# ESP32-WROOM32D_Module.net
KiCad netlist of a schematic drawn in Altium Designer
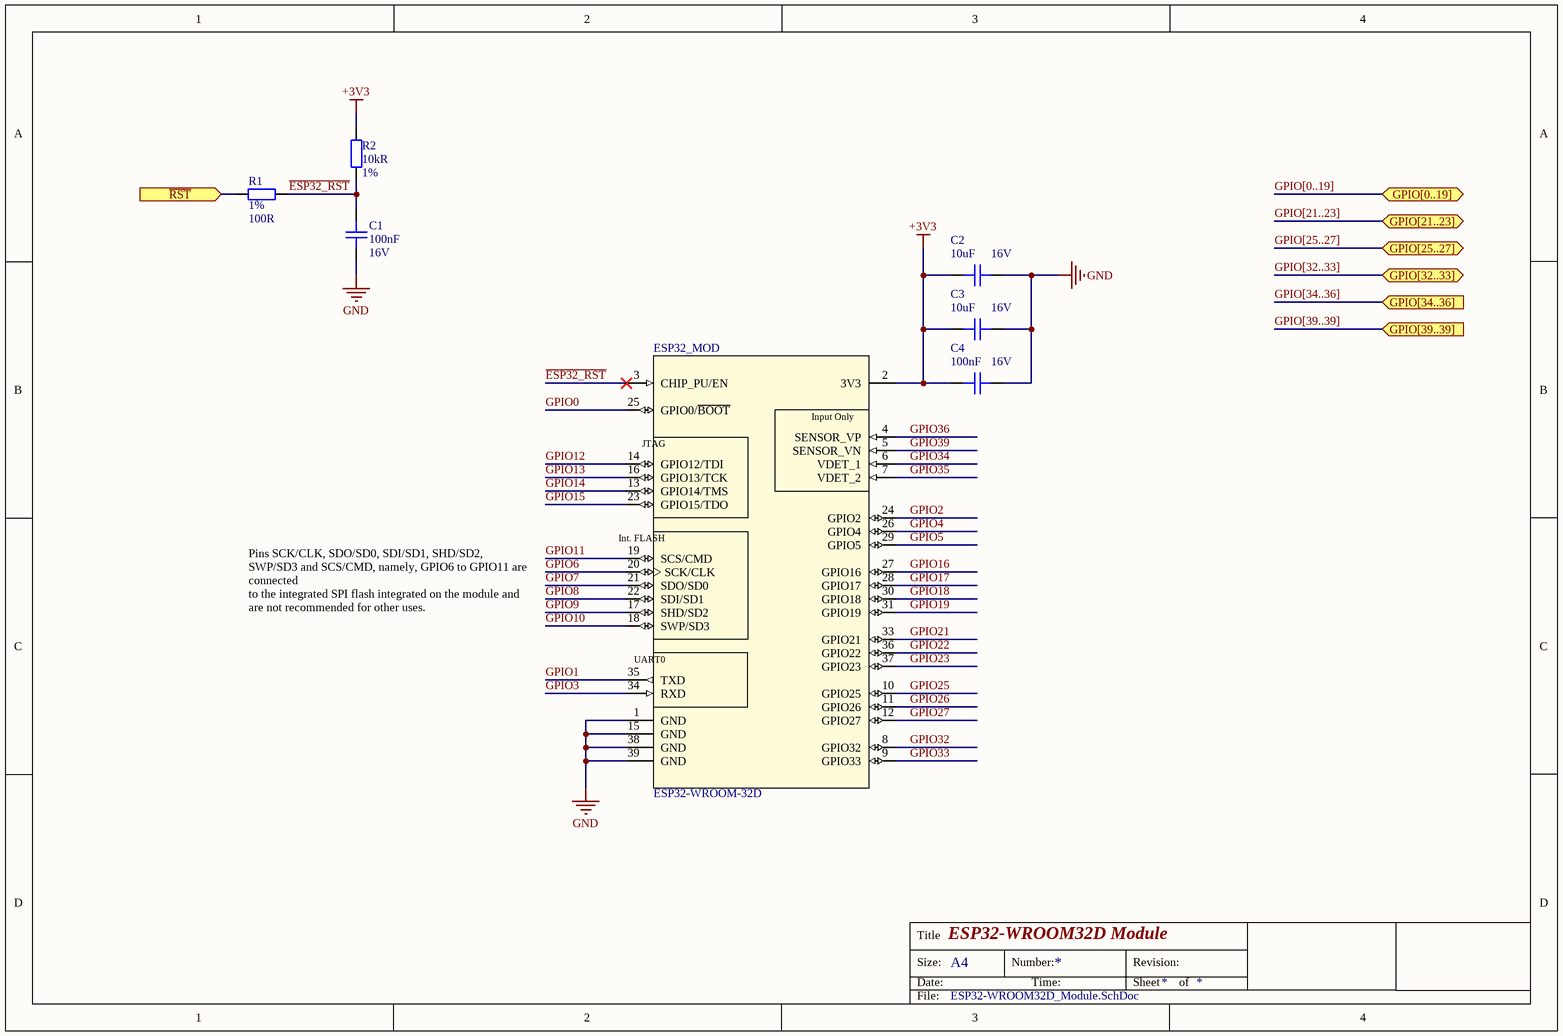
[diagram p0: ESP32-WROOM32D_Module.SchDoc]

(export (version "E")
  (design (tool "Eeschema 10.0.6"))
  (components
    (comp (ref "C1")
      (value "CAP CER 0.1UF 16V X7R 0402")
      (footprint "C0402")
      (description "0.1µF ±10% 16V Ceramic Capacitor X7R 0402 (1005 Metric)")
      (fields
        (field (name "MANUFACTURER PART NUMBER") "CC0402KRX7R7BB104")
        (field (name "MANUFACTURER") "Yageo")
        (field (name "CAPACITANCE") "100nF")
        (field (name "VOLTAGE") "16V")
      )
      (libsource (lib "capacitors_smd") (part "CAP CER 0.1UF 16V X7R 0402"))
    )
    (comp (ref "C2")
      (value "CAP CER 10UF 16V X5R 0603")
      (footprint "C0603")
      (description "10µF ±10% 16V Ceramic Capacitor X5R 0603 (1608 Metric)")
      (fields
        (field (name "MANUFACTURER") "Murata")
        (field (name "MANUFACTURER PART NUMBER") "GRM188R61C106KAALJ")
        (field (name "CAPACITANCE") "10uF")
        (field (name "VOLTAGE RATING") "16V")
      )
      (libsource (lib "capacitors_smd") (part "CAP CER 10UF 16V X5R 0603"))
    )
    (comp (ref "C3")
      (value "CAP CER 10UF 16V X5R 0603")
      (footprint "C0603")
      (description "10µF ±10% 16V Ceramic Capacitor X5R 0603 (1608 Metric)")
      (fields
        (field (name "MANUFACTURER") "Murata")
        (field (name "MANUFACTURER PART NUMBER") "GRM188R61C106KAALJ")
        (field (name "CAPACITANCE") "10uF")
        (field (name "VOLTAGE RATING") "16V")
      )
      (libsource (lib "capacitors_smd") (part "CAP CER 10UF 16V X5R 0603"))
    )
    (comp (ref "C4")
      (value "CAP CER 0.1UF 16V X7R 0402")
      (footprint "C0402")
      (description "0.1µF ±10% 16V Ceramic Capacitor X7R 0402 (1005 Metric)")
      (fields
        (field (name "MANUFACTURER PART NUMBER") "CC0402KRX7R7BB104")
        (field (name "MANUFACTURER") "Yageo")
        (field (name "CAPACITANCE") "100nF")
        (field (name "VOLTAGE") "16V")
      )
      (libsource (lib "capacitors_smd") (part "CAP CER 0.1UF 16V X7R 0402"))
    )
    (comp (ref "ESP32_MOD")
      (value "ESP32-WROOM-32D")
      (footprint "MODULE_ESP32-WROOM-32D")
      (fields (field (name "MANUFACTURER") "Espressif Systems"))
      (libsource (lib "BLDC_Motor_Driver") (part "MOD ESP32-WROOM-32D TRACE ANT SMD"))
    )
    (comp (ref "R1")
      (value "RES SMD 100 OHM 1% 1/16W 0402")
      (footprint "R0402")
      (description "100 Ohms ±1% 0.063W, 1/16W Chip Resistor 0402 (1005 Metric) Moisture Resistant Thick Film")
      (fields
        (field (name "MANUFACTURER PART NUMBER") "RC0402FR-07100RL")
        (field (name "MANUFACTURER") "Yageo")
        (field (name "TOLERANCE") "1%")
        (field (name "RESISTANCE") "100R")
      )
      (libsource (lib "resistors_smd") (part "RES SMD 100 OHM 1% 1/16W 0402"))
    )
    (comp (ref "R2")
      (value "RES SMD 10K OHM 1% 1/16W 0402")
      (footprint "R0402")
      (description "10 kOhms ±1% 0.063W, 1/16W Chip Resistor 0402 (1005 Metric) Moisture Resistant Thick Film")
      (fields
        (field (name "MANUFACTURER PART NUMBER") "RC0402FR-0710KP")
        (field (name "MANUFACTURER") "Yageo")
        (field (name "RESISTANCE") "10kR")
        (field (name "TOLERANCE") "1%")
      )
      (libsource (lib "resistors_smd") (part "RES SMD 10K OHM 1% 1/16W 0402"))
    )
  )
  (nets
    (net (code "2") (name "+3V3") (class "Default")
      (node (ref "C2") (pin "2") (pinfunction "2_2") (pintype "passive"))
      (node (ref "C3") (pin "2") (pinfunction "2_2") (pintype "passive"))
      (node (ref "C4") (pin "2") (pinfunction "2_2") (pintype "passive"))
      (node (ref "ESP32_MOD") (pin "2") (pinfunction "3V3_2") (pintype "power_in"))
      (node (ref "R2") (pin "1") (pinfunction "1_1") (pintype "passive"))
    )
    (net (code "3") (name "/ESP32_RST") (class "Default")
      (node (ref "C1") (pin "2") (pinfunction "2_2") (pintype "passive"))
      (node (ref "ESP32_MOD") (pin "3") (pinfunction "CHIP_PU/EN_3") (pintype "input"))
      (node (ref "R1") (pin "1") (pinfunction "1_1") (pintype "passive"))
      (node (ref "R2") (pin "2") (pinfunction "2_2") (pintype "passive"))
    )
    (net (code "4") (name "/GPIO0") (class "Default")
      (node (ref "ESP32_MOD") (pin "25") (pinfunction "GPIO0/~{BOOT}_25") (pintype "bidirectional"))
    )
    (net (code "5") (name "/GPIO1") (class "Default")
      (node (ref "ESP32_MOD") (pin "35") (pinfunction "TXD_35") (pintype "output"))
    )
    (net (code "6") (name "/GPIO2") (class "Default")
      (node (ref "ESP32_MOD") (pin "24") (pinfunction "GPIO2_24") (pintype "bidirectional"))
    )
    (net (code "7") (name "/GPIO3") (class "Default")
      (node (ref "ESP32_MOD") (pin "34") (pinfunction "RXD_34") (pintype "input"))
    )
    (net (code "8") (name "/GPIO4") (class "Default")
      (node (ref "ESP32_MOD") (pin "26") (pinfunction "GPIO4_26") (pintype "bidirectional"))
    )
    (net (code "9") (name "/GPIO5") (class "Default")
      (node (ref "ESP32_MOD") (pin "29") (pinfunction "GPIO5_29") (pintype "bidirectional"))
    )
    (net (code "10") (name "/GPIO6") (class "Default")
      (node (ref "ESP32_MOD") (pin "20") (pinfunction "SCK/CLK_20") (pintype "bidirectional"))
    )
    (net (code "11") (name "/GPIO7") (class "Default")
      (node (ref "ESP32_MOD") (pin "21") (pinfunction "SDO/SD0_21") (pintype "bidirectional"))
    )
    (net (code "12") (name "/GPIO8") (class "Default")
      (node (ref "ESP32_MOD") (pin "22") (pinfunction "SDI/SD1_22") (pintype "bidirectional"))
    )
    (net (code "13") (name "/GPIO9") (class "Default")
      (node (ref "ESP32_MOD") (pin "17") (pinfunction "SHD/SD2_17") (pintype "bidirectional"))
    )
    (net (code "14") (name "/GPIO10") (class "Default")
      (node (ref "ESP32_MOD") (pin "18") (pinfunction "SWP/SD3_18") (pintype "bidirectional"))
    )
    (net (code "15") (name "/GPIO11") (class "Default")
      (node (ref "ESP32_MOD") (pin "19") (pinfunction "SCS/CMD_19") (pintype "bidirectional"))
    )
    (net (code "16") (name "/GPIO12") (class "Default")
      (node (ref "ESP32_MOD") (pin "14") (pinfunction "GPIO12/TDI_14") (pintype "bidirectional"))
    )
    (net (code "17") (name "/GPIO13") (class "Default")
      (node (ref "ESP32_MOD") (pin "16") (pinfunction "GPIO13/TCK_16") (pintype "bidirectional"))
    )
    (net (code "18") (name "/GPIO14") (class "Default")
      (node (ref "ESP32_MOD") (pin "13") (pinfunction "GPIO14/TMS_13") (pintype "bidirectional"))
    )
    (net (code "19") (name "/GPIO15") (class "Default")
      (node (ref "ESP32_MOD") (pin "23") (pinfunction "GPIO15/TDO_23") (pintype "bidirectional"))
    )
    (net (code "20") (name "/GPIO16") (class "Default")
      (node (ref "ESP32_MOD") (pin "27") (pinfunction "GPIO16_27") (pintype "bidirectional"))
    )
    (net (code "21") (name "/GPIO17") (class "Default")
      (node (ref "ESP32_MOD") (pin "28") (pinfunction "GPIO17_28") (pintype "bidirectional"))
    )
    (net (code "22") (name "/GPIO18") (class "Default")
      (node (ref "ESP32_MOD") (pin "30") (pinfunction "GPIO18_30") (pintype "bidirectional"))
    )
    (net (code "23") (name "/GPIO19") (class "Default")
      (node (ref "ESP32_MOD") (pin "31") (pinfunction "GPIO19_31") (pintype "bidirectional"))
    )
    (net (code "24") (name "/GPIO21") (class "Default")
      (node (ref "ESP32_MOD") (pin "33") (pinfunction "GPIO21_33") (pintype "bidirectional"))
    )
    (net (code "25") (name "/GPIO22") (class "Default")
      (node (ref "ESP32_MOD") (pin "36") (pinfunction "GPIO22_36") (pintype "bidirectional"))
    )
    (net (code "26") (name "/GPIO23") (class "Default")
      (node (ref "ESP32_MOD") (pin "37") (pinfunction "GPIO23_37") (pintype "bidirectional"))
    )
    (net (code "27") (name "/GPIO25") (class "Default")
      (node (ref "ESP32_MOD") (pin "10") (pinfunction "GPIO25_10") (pintype "bidirectional"))
    )
    (net (code "28") (name "/GPIO26") (class "Default")
      (node (ref "ESP32_MOD") (pin "11") (pinfunction "GPIO26_11") (pintype "bidirectional"))
    )
    (net (code "29") (name "/GPIO27") (class "Default")
      (node (ref "ESP32_MOD") (pin "12") (pinfunction "GPIO27_12") (pintype "bidirectional"))
    )
    (net (code "30") (name "/GPIO32") (class "Default")
      (node (ref "ESP32_MOD") (pin "8") (pinfunction "GPIO32_8") (pintype "bidirectional"))
    )
    (net (code "31") (name "/GPIO33") (class "Default")
      (node (ref "ESP32_MOD") (pin "9") (pinfunction "GPIO33_9") (pintype "bidirectional"))
    )
    (net (code "32") (name "/GPIO34") (class "Default")
      (node (ref "ESP32_MOD") (pin "6") (pinfunction "VDET_1_6") (pintype "input"))
    )
    (net (code "33") (name "/GPIO35") (class "Default")
      (node (ref "ESP32_MOD") (pin "7") (pinfunction "VDET_2_7") (pintype "input"))
    )
    (net (code "34") (name "/GPIO36") (class "Default")
      (node (ref "ESP32_MOD") (pin "4") (pinfunction "SENSOR_VP_4") (pintype "input"))
    )
    (net (code "35") (name "/GPIO39") (class "Default")
      (node (ref "ESP32_MOD") (pin "5") (pinfunction "SENSOR_VN_5") (pintype "input"))
    )
    (net (code "41") (name "/RST") (class "Default")
      (node (ref "R1") (pin "2") (pinfunction "2_2") (pintype "passive"))
    )
    (net (code "43") (name "GND") (class "Default")
      (node (ref "C1") (pin "1") (pinfunction "1_1") (pintype "passive"))
      (node (ref "C2") (pin "1") (pinfunction "1_1") (pintype "passive"))
      (node (ref "C3") (pin "1") (pinfunction "1_1") (pintype "passive"))
      (node (ref "C4") (pin "1") (pinfunction "1_1") (pintype "passive"))
      (node (ref "ESP32_MOD") (pin "1") (pinfunction "GND_1") (pintype "power_in"))
      (node (ref "ESP32_MOD") (pin "15") (pinfunction "GND_15") (pintype "power_in"))
      (node (ref "ESP32_MOD") (pin "38") (pinfunction "GND_38") (pintype "power_in"))
      (node (ref "ESP32_MOD") (pin "39") (pinfunction "GND_39") (pintype "power_in"))
    )
  )
)
